# lx9io.net
KiCad netlist of a schematic drawn in EAGLE
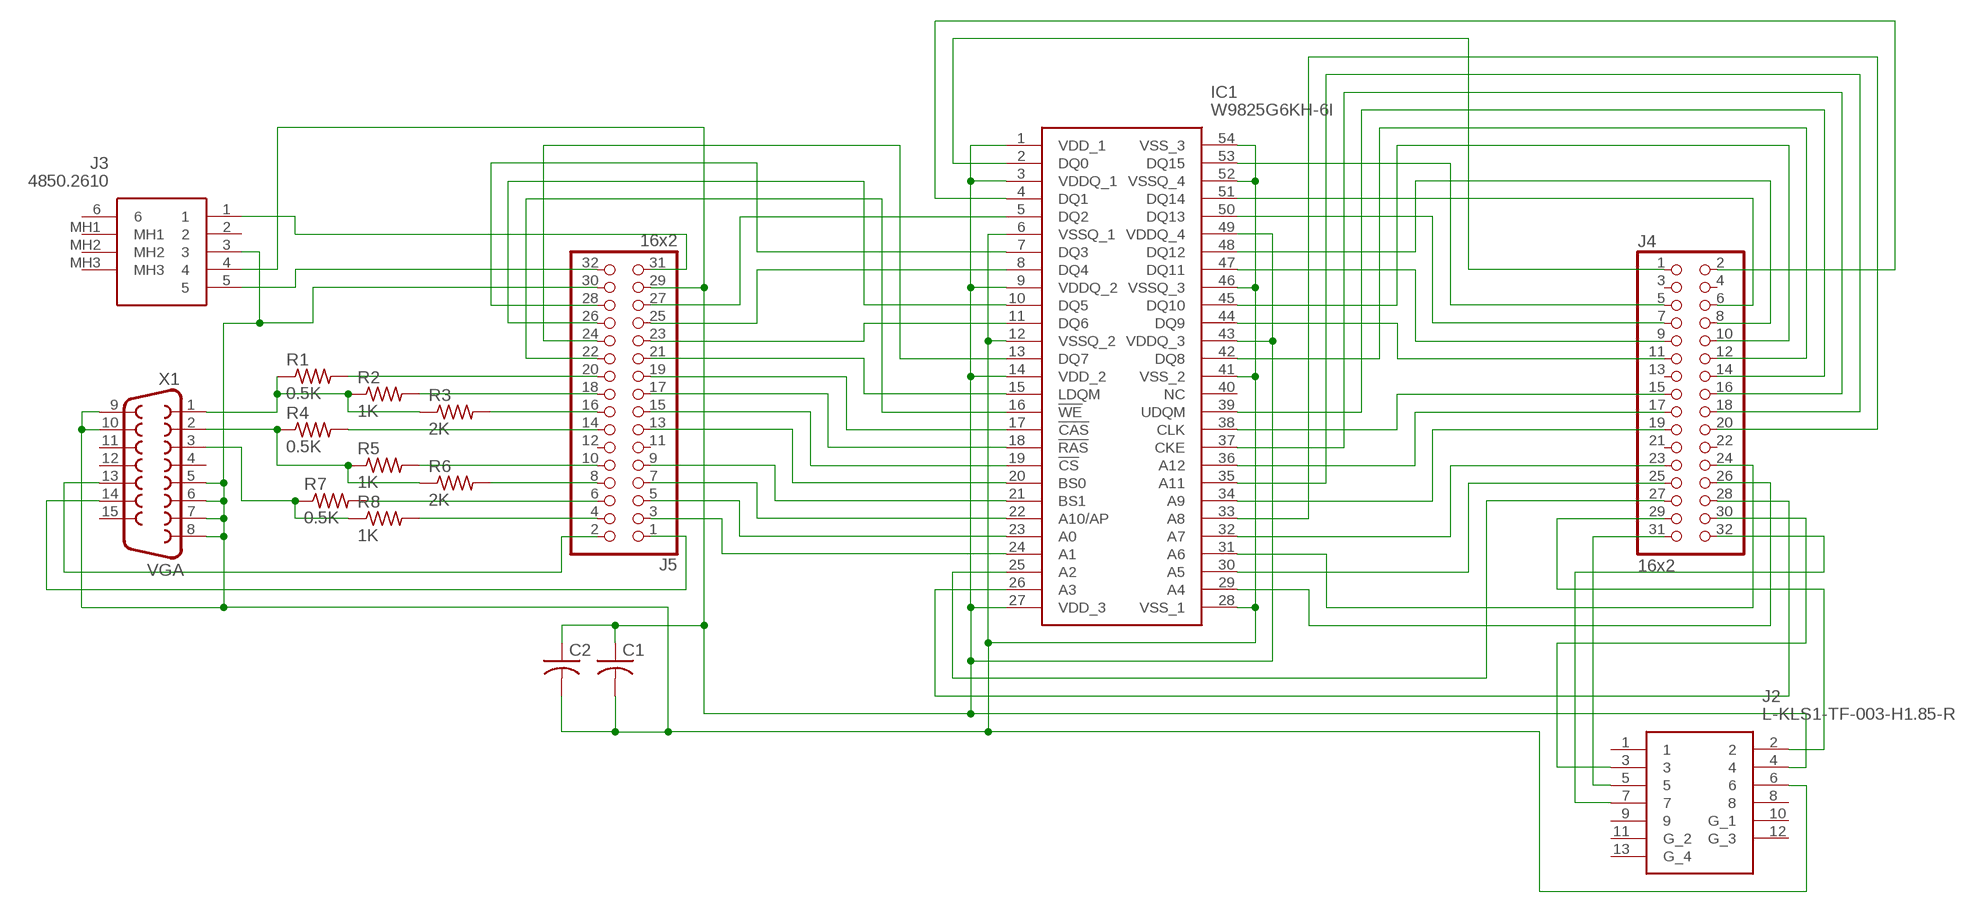
[diagram p0: schematic, sheet 1]

(export (version "E")
  (design (tool "Eeschema 10.0.6"))
  (components
    (comp (ref "C1")
      (value "C-USC0805")
      (footprint "eagle-import:C0805")
      (libsource (lib "eagle-import") (part "C-USC0805"))
    )
    (comp (ref "C2")
      (value "C-USC0805")
      (footprint "eagle-import:C0805")
      (libsource (lib "eagle-import") (part "C-USC0805"))
    )
    (comp (ref "IC1")
      (value "W9825G6KH-6I")
      (footprint "eagle-import:SOP80P1176X120-54N")
      (fields
        (field (name "MOUSER_PART_NUMBER") "454-W9825G6KH-6I")
        (field (name "RS_PART_NUMBER") "1882632")
      )
      (libsource (lib "eagle-import") (part "W9825G6KH-6I"))
    )
    (comp (ref "J2")
      (value "L-KLS1-TF-003-H1.85-R")
      (footprint "eagle-import:L-KLS1-TF-003-H1.85-R")
      (libsource (lib "eagle-import") (part "L-KLS1-TF-003-H1.85-R"))
    )
    (comp (ref "J3")
      (value "4850.2610")
      (footprint "eagle-import:48502610")
      (fields (field (name "MOUSER_PART_NUMBER") "693-4850.2610"))
      (libsource (lib "eagle-import") (part "4850.2610"))
    )
    (comp (ref "J4")
      (value "16x2")
      (footprint "eagle-import:2X16")
      (libsource (lib "eagle-import") (part "PINHD-2X16"))
    )
    (comp (ref "J5")
      (value "16x2")
      (footprint "eagle-import:2X16")
      (libsource (lib "eagle-import") (part "PINHD-2X16"))
    )
    (comp (ref "R1")
      (value "0.5K")
      (footprint "eagle-import:M0805")
      (libsource (lib "eagle-import") (part "R-US_M0805"))
    )
    (comp (ref "R2")
      (value "1K")
      (footprint "eagle-import:M0805")
      (libsource (lib "eagle-import") (part "R-US_M0805"))
    )
    (comp (ref "R3")
      (value "2K")
      (footprint "eagle-import:M0805")
      (libsource (lib "eagle-import") (part "R-US_M0805"))
    )
    (comp (ref "R4")
      (value "0.5K")
      (footprint "eagle-import:M0805")
      (libsource (lib "eagle-import") (part "R-US_M0805"))
    )
    (comp (ref "R5")
      (value "1K")
      (footprint "eagle-import:M0805")
      (libsource (lib "eagle-import") (part "R-US_M0805"))
    )
    (comp (ref "R6")
      (value "2K")
      (footprint "eagle-import:M0805")
      (libsource (lib "eagle-import") (part "R-US_M0805"))
    )
    (comp (ref "R7")
      (value "0.5K")
      (footprint "eagle-import:M0805")
      (libsource (lib "eagle-import") (part "R-US_M0805"))
    )
    (comp (ref "R8")
      (value "1K")
      (footprint "eagle-import:M0805")
      (libsource (lib "eagle-import") (part "R-US_M0805"))
    )
    (comp (ref "X1")
      (value "VGA")
      (footprint "eagle-import:HDF15H")
      (libsource (lib "eagle-import") (part "F15HDH"))
    )
  )
  (nets
    (net (code "1") (name "Net-(IC1-A0)") (class "Default")
      (node (ref "IC1") (pin "23") (pinfunction "A0_23") (pintype "bidirectional"))
      (node (ref "J5") (pin "5") (pinfunction "5_5") (pintype "passive"))
    )
    (net (code "2") (name "Net-(IC1-A1)") (class "Default")
      (node (ref "IC1") (pin "24") (pinfunction "A1_24") (pintype "bidirectional"))
      (node (ref "J5") (pin "3") (pinfunction "3_3") (pintype "passive"))
    )
    (net (code "3") (name "Net-(IC1-A2)") (class "Default")
      (node (ref "IC1") (pin "25") (pinfunction "A2_25") (pintype "bidirectional"))
      (node (ref "J4") (pin "27") (pinfunction "27_27") (pintype "passive"))
    )
    (net (code "4") (name "Net-(IC1-A3)") (class "Default")
      (node (ref "IC1") (pin "26") (pinfunction "A3_26") (pintype "bidirectional"))
      (node (ref "J4") (pin "28") (pinfunction "28_28") (pintype "passive"))
    )
    (net (code "5") (name "Net-(IC1-A4)") (class "Default")
      (node (ref "IC1") (pin "29") (pinfunction "A4_29") (pintype "bidirectional"))
      (node (ref "J4") (pin "26") (pinfunction "26_26") (pintype "passive"))
    )
    (net (code "6") (name "Net-(IC1-A5)") (class "Default")
      (node (ref "IC1") (pin "30") (pinfunction "A5_30") (pintype "bidirectional"))
      (node (ref "J4") (pin "25") (pinfunction "25_25") (pintype "passive"))
    )
    (net (code "7") (name "Net-(IC1-A6)") (class "Default")
      (node (ref "IC1") (pin "31") (pinfunction "A6_31") (pintype "bidirectional"))
      (node (ref "J4") (pin "24") (pinfunction "24_24") (pintype "passive"))
    )
    (net (code "8") (name "Net-(IC1-A7)") (class "Default")
      (node (ref "IC1") (pin "32") (pinfunction "A7_32") (pintype "bidirectional"))
      (node (ref "J4") (pin "23") (pinfunction "23_23") (pintype "passive"))
    )
    (net (code "9") (name "Net-(IC1-A8)") (class "Default")
      (node (ref "IC1") (pin "33") (pinfunction "A8_33") (pintype "bidirectional"))
      (node (ref "J4") (pin "20") (pinfunction "20_20") (pintype "passive"))
    )
    (net (code "10") (name "Net-(IC1-A9)") (class "Default")
      (node (ref "IC1") (pin "34") (pinfunction "A9_34") (pintype "bidirectional"))
      (node (ref "J4") (pin "19") (pinfunction "19_19") (pintype "passive"))
    )
    (net (code "11") (name "Net-(IC1-A10{slash}AP)") (class "Default")
      (node (ref "IC1") (pin "22") (pinfunction "A10/AP_22") (pintype "bidirectional"))
      (node (ref "J5") (pin "7") (pinfunction "7_7") (pintype "passive"))
    )
    (net (code "12") (name "Net-(IC1-A11)") (class "Default")
      (node (ref "IC1") (pin "35") (pinfunction "A11_35") (pintype "bidirectional"))
      (node (ref "J4") (pin "18") (pinfunction "18_18") (pintype "passive"))
    )
    (net (code "13") (name "Net-(IC1-A12)") (class "Default")
      (node (ref "IC1") (pin "36") (pinfunction "A12_36") (pintype "bidirectional"))
      (node (ref "J4") (pin "17") (pinfunction "17_17") (pintype "passive"))
    )
    (net (code "14") (name "Net-(IC1-BS0)") (class "Default")
      (node (ref "IC1") (pin "20") (pinfunction "BS0_20") (pintype "bidirectional"))
      (node (ref "J5") (pin "13") (pinfunction "13_13") (pintype "passive"))
    )
    (net (code "15") (name "Net-(IC1-BS1)") (class "Default")
      (node (ref "IC1") (pin "21") (pinfunction "BS1_21") (pintype "bidirectional"))
      (node (ref "J5") (pin "9") (pinfunction "9_9") (pintype "passive"))
    )
    (net (code "16") (name "Net-(IC1-CKE)") (class "Default")
      (node (ref "IC1") (pin "37") (pinfunction "CKE_37") (pintype "bidirectional"))
      (node (ref "J4") (pin "16") (pinfunction "16_16") (pintype "passive"))
    )
    (net (code "17") (name "Net-(IC1-CLK)") (class "Default")
      (node (ref "IC1") (pin "38") (pinfunction "CLK_38") (pintype "bidirectional"))
      (node (ref "J4") (pin "15") (pinfunction "15_15") (pintype "passive"))
    )
    (net (code "18") (name "Net-(IC1-DQ0)") (class "Default")
      (node (ref "IC1") (pin "2") (pinfunction "DQ0_2") (pintype "bidirectional"))
      (node (ref "J4") (pin "1") (pinfunction "1_1") (pintype "passive"))
    )
    (net (code "19") (name "Net-(IC1-DQ1)") (class "Default")
      (node (ref "IC1") (pin "4") (pinfunction "DQ1_4") (pintype "bidirectional"))
      (node (ref "J4") (pin "2") (pinfunction "2_2") (pintype "passive"))
    )
    (net (code "20") (name "Net-(IC1-DQ2)") (class "Default")
      (node (ref "IC1") (pin "5") (pinfunction "DQ2_5") (pintype "bidirectional"))
      (node (ref "J5") (pin "27") (pinfunction "27_27") (pintype "passive"))
    )
    (net (code "21") (name "Net-(IC1-DQ3)") (class "Default")
      (node (ref "IC1") (pin "7") (pinfunction "DQ3_7") (pintype "bidirectional"))
      (node (ref "J5") (pin "28") (pinfunction "28_28") (pintype "passive"))
    )
    (net (code "22") (name "Net-(IC1-DQ4)") (class "Default")
      (node (ref "IC1") (pin "8") (pinfunction "DQ4_8") (pintype "bidirectional"))
      (node (ref "J5") (pin "25") (pinfunction "25_25") (pintype "passive"))
    )
    (net (code "23") (name "Net-(IC1-DQ5)") (class "Default")
      (node (ref "IC1") (pin "10") (pinfunction "DQ5_10") (pintype "bidirectional"))
      (node (ref "J5") (pin "26") (pinfunction "26_26") (pintype "passive"))
    )
    (net (code "24") (name "Net-(IC1-DQ6)") (class "Default")
      (node (ref "IC1") (pin "11") (pinfunction "DQ6_11") (pintype "bidirectional"))
      (node (ref "J5") (pin "23") (pinfunction "23_23") (pintype "passive"))
    )
    (net (code "25") (name "Net-(IC1-DQ7)") (class "Default")
      (node (ref "IC1") (pin "13") (pinfunction "DQ7_13") (pintype "bidirectional"))
      (node (ref "J5") (pin "24") (pinfunction "24_24") (pintype "passive"))
    )
    (net (code "26") (name "Net-(IC1-DQ8)") (class "Default")
      (node (ref "IC1") (pin "42") (pinfunction "DQ8_42") (pintype "bidirectional"))
      (node (ref "J4") (pin "12") (pinfunction "12_12") (pintype "passive"))
    )
    (net (code "27") (name "Net-(IC1-DQ9)") (class "Default")
      (node (ref "IC1") (pin "44") (pinfunction "DQ9_44") (pintype "bidirectional"))
      (node (ref "J4") (pin "11") (pinfunction "11_11") (pintype "passive"))
    )
    (net (code "28") (name "Net-(IC1-DQ10)") (class "Default")
      (node (ref "IC1") (pin "45") (pinfunction "DQ10_45") (pintype "bidirectional"))
      (node (ref "J4") (pin "10") (pinfunction "10_10") (pintype "passive"))
    )
    (net (code "29") (name "Net-(IC1-DQ11)") (class "Default")
      (node (ref "IC1") (pin "47") (pinfunction "DQ11_47") (pintype "bidirectional"))
      (node (ref "J4") (pin "9") (pinfunction "9_9") (pintype "passive"))
    )
    (net (code "30") (name "Net-(IC1-DQ12)") (class "Default")
      (node (ref "IC1") (pin "48") (pinfunction "DQ12_48") (pintype "bidirectional"))
      (node (ref "J4") (pin "8") (pinfunction "8_8") (pintype "passive"))
    )
    (net (code "31") (name "Net-(IC1-DQ13)") (class "Default")
      (node (ref "IC1") (pin "50") (pinfunction "DQ13_50") (pintype "bidirectional"))
      (node (ref "J4") (pin "7") (pinfunction "7_7") (pintype "passive"))
    )
    (net (code "32") (name "Net-(IC1-DQ14)") (class "Default")
      (node (ref "IC1") (pin "51") (pinfunction "DQ14_51") (pintype "bidirectional"))
      (node (ref "J4") (pin "6") (pinfunction "6_6") (pintype "passive"))
    )
    (net (code "33") (name "Net-(IC1-DQ15)") (class "Default")
      (node (ref "IC1") (pin "53") (pinfunction "DQ15_53") (pintype "bidirectional"))
      (node (ref "J4") (pin "5") (pinfunction "5_5") (pintype "passive"))
    )
    (net (code "34") (name "Net-(IC1-LDQM)") (class "Default")
      (node (ref "IC1") (pin "15") (pinfunction "LDQM_15") (pintype "bidirectional"))
      (node (ref "J5") (pin "21") (pinfunction "21_21") (pintype "passive"))
    )
    (net (code "35") (name "Net-(IC1-UDQM)") (class "Default")
      (node (ref "IC1") (pin "39") (pinfunction "UDQM_39") (pintype "bidirectional"))
      (node (ref "J4") (pin "14") (pinfunction "14_14") (pintype "passive"))
    )
    (net (code "36") (name "Net-(IC1-VDDQ_1)") (class "Default")
      (node (ref "C1") (pin "1") (pinfunction "1_1") (pintype "passive"))
      (node (ref "C2") (pin "1") (pinfunction "1_1") (pintype "passive"))
      (node (ref "IC1") (pin "1") (pinfunction "VDD_1_1") (pintype "bidirectional"))
      (node (ref "IC1") (pin "14") (pinfunction "VDD_2_14") (pintype "bidirectional"))
      (node (ref "IC1") (pin "27") (pinfunction "VDD_3_27") (pintype "bidirectional"))
      (node (ref "IC1") (pin "3") (pinfunction "VDDQ_1_3") (pintype "bidirectional"))
      (node (ref "IC1") (pin "43") (pinfunction "VDDQ_3_43") (pintype "bidirectional"))
      (node (ref "IC1") (pin "49") (pinfunction "VDDQ_4_49") (pintype "bidirectional"))
      (node (ref "IC1") (pin "9") (pinfunction "VDDQ_2_9") (pintype "bidirectional"))
      (node (ref "J2") (pin "4") (pinfunction "4_4") (pintype "bidirectional"))
      (node (ref "J3") (pin "4") (pinfunction "4_4") (pintype "bidirectional"))
      (node (ref "J5") (pin "29") (pinfunction "29_29") (pintype "passive"))
    )
    (net (code "37") (name "Net-(IC1-VSSQ_1)") (class "Default")
      (node (ref "C1") (pin "2") (pinfunction "2_2") (pintype "passive"))
      (node (ref "C2") (pin "2") (pinfunction "2_2") (pintype "passive"))
      (node (ref "IC1") (pin "12") (pinfunction "VSSQ_2_12") (pintype "bidirectional"))
      (node (ref "IC1") (pin "28") (pinfunction "VSS_1_28") (pintype "bidirectional"))
      (node (ref "IC1") (pin "41") (pinfunction "VSS_2_41") (pintype "bidirectional"))
      (node (ref "IC1") (pin "46") (pinfunction "VSSQ_3_46") (pintype "bidirectional"))
      (node (ref "IC1") (pin "52") (pinfunction "VSSQ_4_52") (pintype "bidirectional"))
      (node (ref "IC1") (pin "54") (pinfunction "VSS_3_54") (pintype "bidirectional"))
      (node (ref "IC1") (pin "6") (pinfunction "VSSQ_1_6") (pintype "bidirectional"))
      (node (ref "J2") (pin "6") (pinfunction "6_6") (pintype "bidirectional"))
      (node (ref "J3") (pin "3") (pinfunction "3_3") (pintype "bidirectional"))
      (node (ref "J5") (pin "30") (pinfunction "30_30") (pintype "passive"))
      (node (ref "X1") (pin "10") (pinfunction "10_10") (pintype "passive"))
      (node (ref "X1") (pin "5") (pinfunction "5_5") (pintype "passive"))
      (node (ref "X1") (pin "6") (pinfunction "6_6") (pintype "passive"))
      (node (ref "X1") (pin "7") (pinfunction "7_7") (pintype "passive"))
      (node (ref "X1") (pin "8") (pinfunction "8_8") (pintype "passive"))
      (node (ref "X1") (pin "9") (pinfunction "9_9") (pintype "passive"))
    )
    (net (code "38") (name "Net-(IC1-~{CAS})") (class "Default")
      (node (ref "IC1") (pin "17") (pinfunction "~{CAS}_17") (pintype "bidirectional"))
      (node (ref "J5") (pin "19") (pinfunction "19_19") (pintype "passive"))
    )
    (net (code "39") (name "Net-(IC1-~{CS})") (class "Default")
      (node (ref "IC1") (pin "19") (pinfunction "~{CS}_19") (pintype "bidirectional"))
      (node (ref "J5") (pin "15") (pinfunction "15_15") (pintype "passive"))
    )
    (net (code "40") (name "Net-(IC1-~{RAS})") (class "Default")
      (node (ref "IC1") (pin "18") (pinfunction "~{RAS}_18") (pintype "bidirectional"))
      (node (ref "J5") (pin "17") (pinfunction "17_17") (pintype "passive"))
    )
    (net (code "41") (name "Net-(IC1-~{WE})") (class "Default")
      (node (ref "IC1") (pin "16") (pinfunction "~{WE}_16") (pintype "bidirectional"))
      (node (ref "J5") (pin "22") (pinfunction "22_22") (pintype "passive"))
    )
    (net (code "42") (name "Net-(J2-Pad2)") (class "Default")
      (node (ref "J2") (pin "2") (pinfunction "2_2") (pintype "bidirectional"))
      (node (ref "J4") (pin "29") (pinfunction "29_29") (pintype "passive"))
    )
    (net (code "43") (name "Net-(J2-Pad3)") (class "Default")
      (node (ref "J2") (pin "3") (pinfunction "3_3") (pintype "bidirectional"))
      (node (ref "J4") (pin "30") (pinfunction "30_30") (pintype "passive"))
    )
    (net (code "44") (name "Net-(J2-Pad5)") (class "Default")
      (node (ref "J2") (pin "5") (pinfunction "5_5") (pintype "bidirectional"))
      (node (ref "J4") (pin "31") (pinfunction "31_31") (pintype "passive"))
    )
    (net (code "45") (name "Net-(J2-Pad7)") (class "Default")
      (node (ref "J2") (pin "7") (pinfunction "7_7") (pintype "bidirectional"))
      (node (ref "J4") (pin "32") (pinfunction "32_32") (pintype "passive"))
    )
    (net (code "46") (name "Net-(J3-Pad1)") (class "Default")
      (node (ref "J3") (pin "1") (pinfunction "1_1") (pintype "bidirectional"))
      (node (ref "J5") (pin "31") (pinfunction "31_31") (pintype "passive"))
    )
    (net (code "47") (name "Net-(J3-Pad5)") (class "Default")
      (node (ref "J3") (pin "5") (pinfunction "5_5") (pintype "bidirectional"))
      (node (ref "J5") (pin "32") (pinfunction "32_32") (pintype "passive"))
    )
    (net (code "48") (name "Net-(J5-Pad1)") (class "Default")
      (node (ref "J5") (pin "1") (pinfunction "1_1") (pintype "passive"))
      (node (ref "X1") (pin "14") (pinfunction "14_14") (pintype "passive"))
    )
    (net (code "49") (name "Net-(J5-Pad2)") (class "Default")
      (node (ref "J5") (pin "2") (pinfunction "2_2") (pintype "passive"))
      (node (ref "X1") (pin "13") (pinfunction "13_13") (pintype "passive"))
    )
    (net (code "50") (name "Net-(J5-Pad4)") (class "Default")
      (node (ref "J5") (pin "4") (pinfunction "4_4") (pintype "passive"))
      (node (ref "R8") (pin "2") (pinfunction "2_2") (pintype "passive"))
    )
    (net (code "51") (name "Net-(J5-Pad6)") (class "Default")
      (node (ref "J5") (pin "6") (pinfunction "6_6") (pintype "passive"))
      (node (ref "R7") (pin "2") (pinfunction "2_2") (pintype "passive"))
    )
    (net (code "52") (name "Net-(J5-Pad8)") (class "Default")
      (node (ref "J5") (pin "8") (pinfunction "8_8") (pintype "passive"))
      (node (ref "R6") (pin "2") (pinfunction "2_2") (pintype "passive"))
    )
    (net (code "53") (name "Net-(J5-Pad10)") (class "Default")
      (node (ref "J5") (pin "10") (pinfunction "10_10") (pintype "passive"))
      (node (ref "R5") (pin "2") (pinfunction "2_2") (pintype "passive"))
    )
    (net (code "54") (name "Net-(J5-Pad14)") (class "Default")
      (node (ref "J5") (pin "14") (pinfunction "14_14") (pintype "passive"))
      (node (ref "R4") (pin "2") (pinfunction "2_2") (pintype "passive"))
    )
    (net (code "55") (name "Net-(J5-Pad16)") (class "Default")
      (node (ref "J5") (pin "16") (pinfunction "16_16") (pintype "passive"))
      (node (ref "R3") (pin "2") (pinfunction "2_2") (pintype "passive"))
    )
    (net (code "56") (name "Net-(J5-Pad18)") (class "Default")
      (node (ref "J5") (pin "18") (pinfunction "18_18") (pintype "passive"))
      (node (ref "R2") (pin "2") (pinfunction "2_2") (pintype "passive"))
    )
    (net (code "57") (name "Net-(J5-Pad20)") (class "Default")
      (node (ref "J5") (pin "20") (pinfunction "20_20") (pintype "passive"))
      (node (ref "R1") (pin "2") (pinfunction "2_2") (pintype "passive"))
    )
    (net (code "58") (name "Net-(R1-Pad1)") (class "Default")
      (node (ref "R1") (pin "1") (pinfunction "1_1") (pintype "passive"))
      (node (ref "R2") (pin "1") (pinfunction "1_1") (pintype "passive"))
      (node (ref "R3") (pin "1") (pinfunction "1_1") (pintype "passive"))
      (node (ref "X1") (pin "1") (pinfunction "1_1") (pintype "passive"))
    )
    (net (code "59") (name "Net-(R4-Pad1)") (class "Default")
      (node (ref "R4") (pin "1") (pinfunction "1_1") (pintype "passive"))
      (node (ref "R5") (pin "1") (pinfunction "1_1") (pintype "passive"))
      (node (ref "R6") (pin "1") (pinfunction "1_1") (pintype "passive"))
      (node (ref "X1") (pin "2") (pinfunction "2_2") (pintype "passive"))
    )
    (net (code "60") (name "Net-(R7-Pad1)") (class "Default")
      (node (ref "R7") (pin "1") (pinfunction "1_1") (pintype "passive"))
      (node (ref "R8") (pin "1") (pinfunction "1_1") (pintype "passive"))
      (node (ref "X1") (pin "3") (pinfunction "3_3") (pintype "passive"))
    )
    (net (code "61") (name "unconnected-(IC1-NC-Pad40)") (class "Default")
      (node (ref "IC1") (pin "40") (pinfunction "NC_40") (pintype "no_connect"))
    )
    (net (code "62") (name "unconnected-(J2-G_1-Pad10)") (class "Default")
      (node (ref "J2") (pin "10") (pinfunction "G_1_10") (pintype "bidirectional"))
    )
    (net (code "63") (name "unconnected-(J2-G_2-Pad11)") (class "Default")
      (node (ref "J2") (pin "11") (pinfunction "G_2_11") (pintype "bidirectional"))
    )
    (net (code "64") (name "unconnected-(J2-G_3-Pad12)") (class "Default")
      (node (ref "J2") (pin "12") (pinfunction "G_3_12") (pintype "bidirectional"))
    )
    (net (code "65") (name "unconnected-(J2-G_4-Pad13)") (class "Default")
      (node (ref "J2") (pin "13") (pinfunction "G_4_13") (pintype "bidirectional"))
    )
    (net (code "66") (name "unconnected-(J2-Pad1)") (class "Default")
      (node (ref "J2") (pin "1") (pinfunction "1_1") (pintype "bidirectional"))
    )
    (net (code "67") (name "unconnected-(J2-Pad8)") (class "Default")
      (node (ref "J2") (pin "8") (pinfunction "8_8") (pintype "bidirectional"))
    )
    (net (code "68") (name "unconnected-(J2-Pad9)") (class "Default")
      (node (ref "J2") (pin "9") (pinfunction "9_9") (pintype "bidirectional"))
    )
    (net (code "69") (name "unconnected-(J3-Pad2)") (class "Default")
      (node (ref "J3") (pin "2") (pinfunction "2_2") (pintype "bidirectional"))
    )
    (net (code "70") (name "unconnected-(J3-Pad6)") (class "Default")
      (node (ref "J3") (pin "6") (pinfunction "6_6") (pintype "bidirectional"))
    )
    (net (code "71") (name "unconnected-(J3-PadMH1)") (class "Default")
      (node (ref "J3") (pin "MH1") (pinfunction "MH1_MH1") (pintype "bidirectional"))
    )
    (net (code "72") (name "unconnected-(J3-PadMH2)") (class "Default")
      (node (ref "J3") (pin "MH2") (pinfunction "MH2_MH2") (pintype "bidirectional"))
    )
    (net (code "73") (name "unconnected-(J3-PadMH3)") (class "Default")
      (node (ref "J3") (pin "MH3") (pinfunction "MH3_MH3") (pintype "bidirectional"))
    )
    (net (code "74") (name "unconnected-(J4-Pad3)") (class "Default")
      (node (ref "J4") (pin "3") (pinfunction "3_3") (pintype "passive"))
    )
    (net (code "75") (name "unconnected-(J4-Pad4)") (class "Default")
      (node (ref "J4") (pin "4") (pinfunction "4_4") (pintype "passive"))
    )
    (net (code "76") (name "unconnected-(J4-Pad13)") (class "Default")
      (node (ref "J4") (pin "13") (pinfunction "13_13") (pintype "passive"))
    )
    (net (code "77") (name "unconnected-(J4-Pad21)") (class "Default")
      (node (ref "J4") (pin "21") (pinfunction "21_21") (pintype "passive"))
    )
    (net (code "78") (name "unconnected-(J4-Pad22)") (class "Default")
      (node (ref "J4") (pin "22") (pinfunction "22_22") (pintype "passive"))
    )
    (net (code "79") (name "unconnected-(J5-Pad11)") (class "Default")
      (node (ref "J5") (pin "11") (pinfunction "11_11") (pintype "passive"))
    )
    (net (code "80") (name "unconnected-(J5-Pad12)") (class "Default")
      (node (ref "J5") (pin "12") (pinfunction "12_12") (pintype "passive"))
    )
    (net (code "81") (name "unconnected-(X1-Pad4)") (class "Default")
      (node (ref "X1") (pin "4") (pinfunction "4_4") (pintype "passive"))
    )
    (net (code "82") (name "unconnected-(X1-Pad11)") (class "Default")
      (node (ref "X1") (pin "11") (pinfunction "11_11") (pintype "passive"))
    )
    (net (code "83") (name "unconnected-(X1-Pad12)") (class "Default")
      (node (ref "X1") (pin "12") (pinfunction "12_12") (pintype "passive"))
    )
    (net (code "84") (name "unconnected-(X1-Pad15)") (class "Default")
      (node (ref "X1") (pin "15") (pinfunction "15_15") (pintype "passive"))
    )
  )
)
